# design.net
KiCad netlist of a schematic drawn in Altium Designer
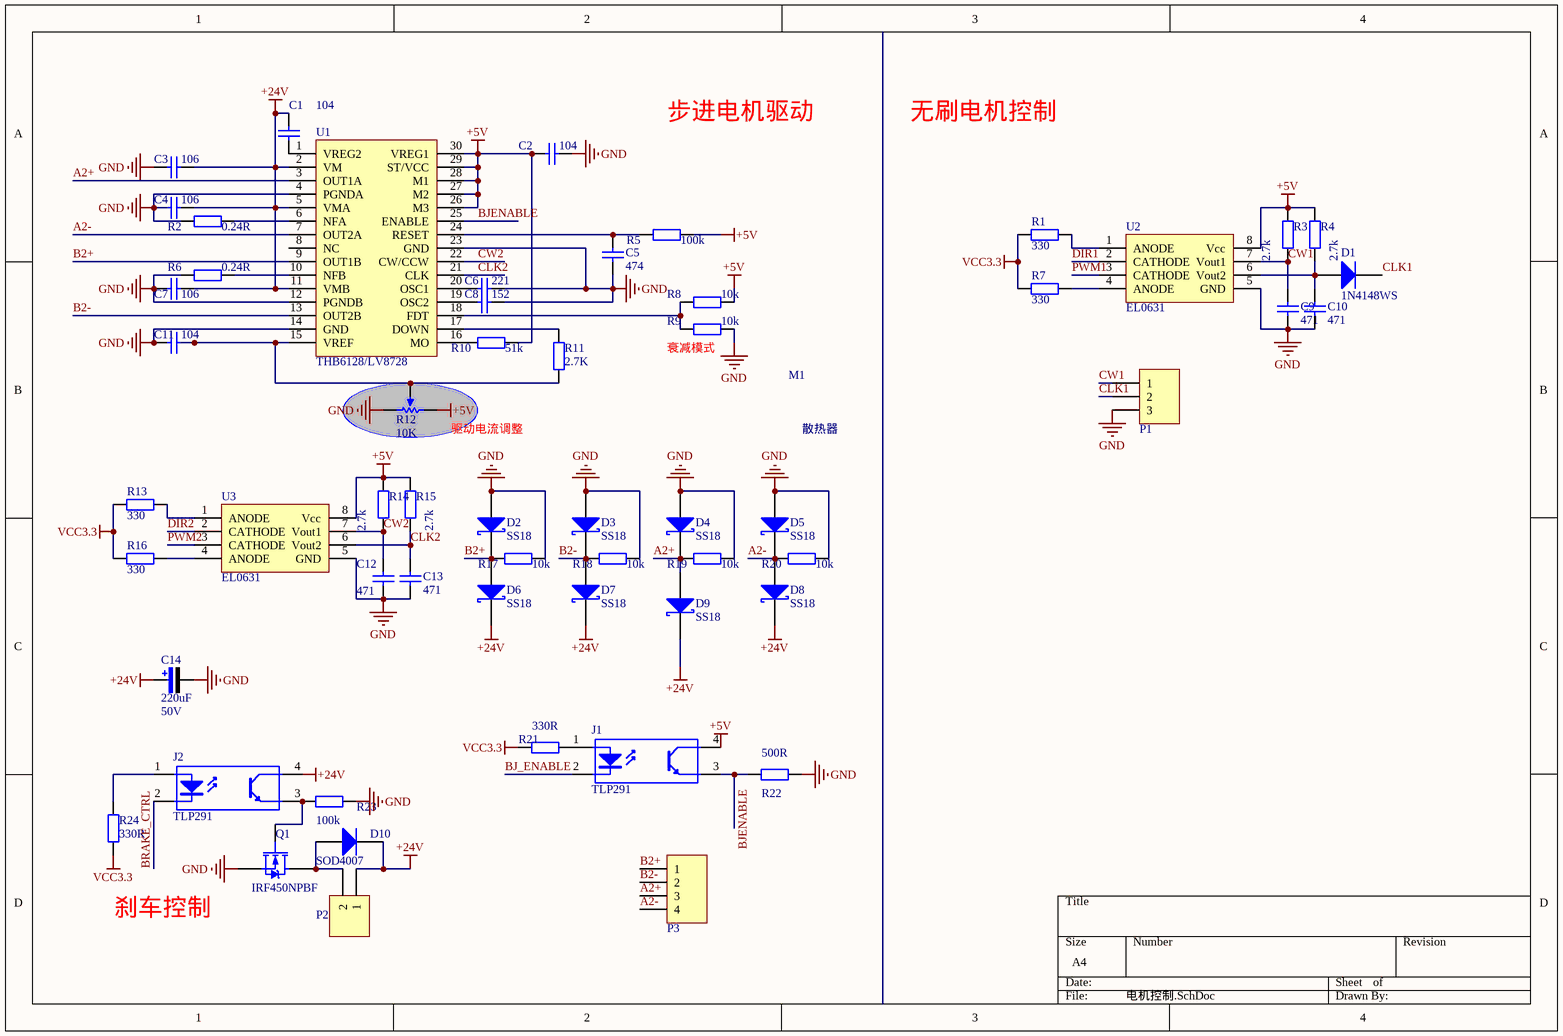
[diagram p0: 电机控制.SchDoc]

(export (version "E")
  (design (tool "Eeschema 10.0.6"))
  (components
    (comp (ref "C1")
      (value "104")
      (footprint "C-RAD-0603")
      (description "无极性电容")
      (fields (field (name "Comment") "Cap") (field (name "PUBLISHER") "Altium Limited"))
      (libsource (lib "Fszhang") (part "Cap"))
    )
    (comp (ref "C2")
      (value "104")
      (footprint "C-RAD-0603")
      (description "无极性电容")
      (fields (field (name "Comment") "Cap") (field (name "PUBLISHER") "Altium Limited"))
      (libsource (lib "Fszhang") (part "Cap"))
    )
    (comp (ref "C3")
      (value "106")
      (footprint "C-RAD-0603")
      (description "无极性电容")
      (fields (field (name "Comment") "Cap") (field (name "PUBLISHER") "Altium Limited"))
      (libsource (lib "Fszhang") (part "Cap"))
    )
    (comp (ref "C4")
      (value "106")
      (footprint "C-RAD-0603")
      (description "无极性电容")
      (fields (field (name "Comment") "Cap") (field (name "PUBLISHER") "Altium Limited"))
      (libsource (lib "Fszhang") (part "Cap"))
    )
    (comp (ref "C5")
      (value "474")
      (footprint "C-RAD-0603")
      (description "无极性电容")
      (fields (field (name "Comment") "Cap") (field (name "PUBLISHER") "Altium Limited"))
      (libsource (lib "Fszhang") (part "Cap"))
    )
    (comp (ref "C6")
      (value "221")
      (footprint "C-RAD-0603")
      (description "无极性电容")
      (fields (field (name "Comment") "Cap") (field (name "PUBLISHER") "Altium Limited"))
      (libsource (lib "Fszhang") (part "Cap"))
    )
    (comp (ref "C7")
      (value "106")
      (footprint "C-RAD-0603")
      (description "无极性电容")
      (fields (field (name "Comment") "Cap") (field (name "PUBLISHER") "Altium Limited"))
      (libsource (lib "Fszhang") (part "Cap"))
    )
    (comp (ref "C8")
      (value "152")
      (footprint "C-RAD-0603")
      (description "无极性电容")
      (fields (field (name "Comment") "Cap") (field (name "PUBLISHER") "Altium Limited"))
      (libsource (lib "Fszhang") (part "Cap"))
    )
    (comp (ref "C9")
      (value "471")
      (footprint "C-RAD-0603")
      (description "无极性电容")
      (fields (field (name "Comment") "Cap") (field (name "PUBLISHER") "Altium Limited"))
      (libsource (lib "Fszhang") (part "Cap"))
    )
    (comp (ref "C10")
      (value "471")
      (footprint "C-RAD-0603")
      (description "无极性电容")
      (fields (field (name "Comment") "Cap") (field (name "PUBLISHER") "Altium Limited"))
      (libsource (lib "Fszhang") (part "Cap"))
    )
    (comp (ref "C11")
      (value "104")
      (footprint "C-RAD-0603")
      (description "无极性电容")
      (fields (field (name "Comment") "Cap") (field (name "PUBLISHER") "Altium Limited"))
      (libsource (lib "Fszhang") (part "Cap"))
    )
    (comp (ref "C12")
      (value "471")
      (footprint "C-RAD-0603")
      (description "无极性电容")
      (fields (field (name "Comment") "Cap") (field (name "PUBLISHER") "Altium Limited"))
      (libsource (lib "Fszhang") (part "Cap"))
    )
    (comp (ref "C13")
      (value "471")
      (footprint "C-RAD-0603")
      (description "无极性电容")
      (fields (field (name "Comment") "Cap") (field (name "PUBLISHER") "Altium Limited"))
      (libsource (lib "Fszhang") (part "Cap"))
    )
    (comp (ref "C14")
      (value "220uF")
      (footprint "C-RB-S10")
      (description "极性电解电容")
      (fields
        (field (name "VOL") "50V")
        (field (name "Comment") "Cap Pol")
        (field (name "PUBLISHER") "Altium Limited")
      )
      (libsource (lib "Fszhang") (part "Cap Pol"))
    )
    (comp (ref "D1")
      (value "Diode")
      (footprint "SOD323")
      (description "二极管")
      (fields (field (name "TYPE") "1N4148WS") (field (name "PUBLISHER") "Altium Limited"))
      (libsource (lib "Fszhang") (part "Diode"))
    )
    (comp (ref "D2")
      (value "D-Schottky")
      (footprint "DIODE-SMA")
      (description "肖特基二极管")
      (fields (field (name "TYPE") "SS18") (field (name "PUBLISHER") "Altium Limited"))
      (libsource (lib "Fszhang") (part "D-Schottky"))
    )
    (comp (ref "D3")
      (value "D-Schottky")
      (footprint "DIODE-SMA")
      (description "肖特基二极管")
      (fields (field (name "TYPE") "SS18") (field (name "PUBLISHER") "Altium Limited"))
      (libsource (lib "Fszhang") (part "D-Schottky"))
    )
    (comp (ref "D4")
      (value "D-Schottky")
      (footprint "DIODE-SMA")
      (description "肖特基二极管")
      (fields (field (name "TYPE") "SS18") (field (name "PUBLISHER") "Altium Limited"))
      (libsource (lib "Fszhang") (part "D-Schottky"))
    )
    (comp (ref "D5")
      (value "D-Schottky")
      (footprint "DIODE-SMA")
      (description "肖特基二极管")
      (fields (field (name "TYPE") "SS18") (field (name "PUBLISHER") "Altium Limited"))
      (libsource (lib "Fszhang") (part "D-Schottky"))
    )
    (comp (ref "D6")
      (value "D-Schottky")
      (footprint "DIODE-SMA")
      (description "肖特基二极管")
      (fields (field (name "TYPE") "SS18") (field (name "PUBLISHER") "Altium Limited"))
      (libsource (lib "Fszhang") (part "D-Schottky"))
    )
    (comp (ref "D7")
      (value "D-Schottky")
      (footprint "DIODE-SMA")
      (description "肖特基二极管")
      (fields (field (name "TYPE") "SS18") (field (name "PUBLISHER") "Altium Limited"))
      (libsource (lib "Fszhang") (part "D-Schottky"))
    )
    (comp (ref "D8")
      (value "D-Schottky")
      (footprint "DIODE-SMA")
      (description "肖特基二极管")
      (fields (field (name "TYPE") "SS18") (field (name "PUBLISHER") "Altium Limited"))
      (libsource (lib "Fszhang") (part "D-Schottky"))
    )
    (comp (ref "D9")
      (value "D-Schottky")
      (footprint "DIODE-SMA")
      (description "肖特基二极管")
      (fields (field (name "TYPE") "SS18") (field (name "PUBLISHER") "Altium Limited"))
      (libsource (lib "Fszhang") (part "D-Schottky"))
    )
    (comp (ref "D10")
      (value "Diode")
      (footprint "SOD123")
      (description "二极管")
      (fields (field (name "TYPE") "SOD4007") (field (name "PUBLISHER") "Altium Limited"))
      (libsource (lib "Fszhang") (part "Diode"))
    )
    (comp (ref "J1")
      (value "TLP291")
      (footprint "SOP127P710X350-4N")
      (description "光耦")
      (fields (field (name "PUBLISHER") "Altium Limited"))
      (libsource (lib "Fszhang") (part "TLP281"))
    )
    (comp (ref "J2")
      (value "TLP291")
      (footprint "SOP127P710X350-4N")
      (description "光耦")
      (fields (field (name "PUBLISHER") "Altium Limited"))
      (libsource (lib "") (part "TLP281_1"))
    )
    (comp (ref "M1")
      (value "散热器")
      (footprint "26*26*10对角37.5")
      (description "26*26*10MM散热器孔距37MM")
      (libsource (lib "RADIATOR") (part "26*26*10散热器"))
    )
    (comp (ref "P1")
      (value "Header 3")
      (footprint "XH2.54*3卧贴")
      (description "接插件")
      (fields (field (name "PUBLISHER") "Altium Limited"))
      (libsource (lib "Fszhang") (part "Header 3"))
    )
    (comp (ref "P2")
      (value "Header 2")
      (footprint "XH2.54*2卧贴")
      (description "接插件")
      (fields (field (name "PUBLISHER") "Altium Limited"))
      (libsource (lib "Fszhang") (part "Header 2"))
    )
    (comp (ref "P3")
      (value "Header 4")
      (footprint "XH2.54*4卧贴")
      (description "接插件")
      (fields (field (name "PUBLISHER") "Altium Limited"))
      (libsource (lib "Fszhang") (part "Header 4"))
    )
    (comp (ref "Q1")
      (value "IRF450NPBF")
      (footprint "TO-263-2")
      (description "N-Channel MOSFET")
      (fields (field (name "PUBLISHER") "Altium Limited"))
      (libsource (lib "Fszhang") (part "MOSFET-N"))
    )
    (comp (ref "R1")
      (value "330")
      (footprint "0603-1")
      (description "贴片电阻")
      (fields (field (name "Comment") "Res1") (field (name "PUBLISHER") "Altium Limited"))
      (libsource (lib "") (part "Res1_1"))
    )
    (comp (ref "R2")
      (value "0.24R")
      (footprint "2512")
      (description "贴片电阻")
      (fields (field (name "Comment") "Res1") (field (name "PUBLISHER") "Altium Limited"))
      (libsource (lib "Fszhang") (part "Res1"))
    )
    (comp (ref "R3")
      (value "2.7k")
      (footprint "0603-1")
      (description "贴片电阻")
      (fields (field (name "Comment") "Res1") (field (name "PUBLISHER") "Altium Limited"))
      (libsource (lib "") (part "Res1_3"))
    )
    (comp (ref "R4")
      (value "2.7k")
      (footprint "0603-1")
      (description "贴片电阻")
      (fields (field (name "Comment") "Res1") (field (name "PUBLISHER") "Altium Limited"))
      (libsource (lib "") (part "Res1_3"))
    )
    (comp (ref "R5")
      (value "100k")
      (footprint "0603-1")
      (description "贴片电阻")
      (fields (field (name "Comment") "Res1") (field (name "PUBLISHER") "Altium Limited"))
      (libsource (lib "Fszhang") (part "Res1"))
    )
    (comp (ref "R6")
      (value "0.24R")
      (footprint "2512")
      (description "贴片电阻")
      (fields (field (name "Comment") "Res1") (field (name "PUBLISHER") "Altium Limited"))
      (libsource (lib "") (part "Res1_1"))
    )
    (comp (ref "R7")
      (value "330")
      (footprint "0603-1")
      (description "贴片电阻")
      (fields (field (name "Comment") "Res1") (field (name "PUBLISHER") "Altium Limited"))
      (libsource (lib "") (part "Res1_1"))
    )
    (comp (ref "R8")
      (value "10k")
      (footprint "0603-1")
      (description "贴片电阻")
      (fields (field (name "Comment") "Res1") (field (name "PUBLISHER") "Altium Limited"))
      (libsource (lib "Fszhang") (part "Res1"))
    )
    (comp (ref "R9")
      (value "10k")
      (footprint "0603-1")
      (description "贴片电阻")
      (fields (field (name "Comment") "Res1") (field (name "PUBLISHER") "Altium Limited"))
      (libsource (lib "Fszhang") (part "Res1"))
    )
    (comp (ref "R10")
      (value "51k")
      (footprint "0603-1")
      (description "贴片电阻")
      (fields (field (name "Comment") "Res1") (field (name "PUBLISHER") "Altium Limited"))
      (libsource (lib "Fszhang") (part "Res1"))
    )
    (comp (ref "R11")
      (value "2.7K")
      (footprint "0603-1")
      (description "贴片电阻")
      (fields (field (name "Comment") "Res1") (field (name "PUBLISHER") "Altium Limited"))
      (libsource (lib "") (part "Res1_2"))
    )
    (comp (ref "R12")
      (value "10K")
      (footprint "VR-3266W")
      (description "精密可调电阻")
      (fields (field (name "Comment") "RPot") (field (name "PUBLISHER") "Altium Limited"))
      (libsource (lib "Fszhang") (part "RPot"))
    )
    (comp (ref "R13")
      (value "330")
      (footprint "0603-1")
      (description "贴片电阻")
      (fields (field (name "Comment") "Res1") (field (name "PUBLISHER") "Altium Limited"))
      (libsource (lib "") (part "Res1_1"))
    )
    (comp (ref "R14")
      (value "2.7k")
      (footprint "0603-1")
      (description "贴片电阻")
      (fields (field (name "Comment") "Res1") (field (name "PUBLISHER") "Altium Limited"))
      (libsource (lib "") (part "Res1_3"))
    )
    (comp (ref "R15")
      (value "2.7k")
      (footprint "0603-1")
      (description "贴片电阻")
      (fields (field (name "Comment") "Res1") (field (name "PUBLISHER") "Altium Limited"))
      (libsource (lib "") (part "Res1_3"))
    )
    (comp (ref "R16")
      (value "330")
      (footprint "0603-1")
      (description "贴片电阻")
      (fields (field (name "Comment") "Res1") (field (name "PUBLISHER") "Altium Limited"))
      (libsource (lib "") (part "Res1_1"))
    )
    (comp (ref "R17")
      (value "10k")
      (footprint "0603-1")
      (description "贴片电阻")
      (fields (field (name "Comment") "Res1") (field (name "PUBLISHER") "Altium Limited"))
      (libsource (lib "Fszhang") (part "Res1"))
    )
    (comp (ref "R18")
      (value "10k")
      (footprint "0603-1")
      (description "贴片电阻")
      (fields (field (name "Comment") "Res1") (field (name "PUBLISHER") "Altium Limited"))
      (libsource (lib "Fszhang") (part "Res1"))
    )
    (comp (ref "R19")
      (value "10k")
      (footprint "0603-1")
      (description "贴片电阻")
      (fields (field (name "Comment") "Res1") (field (name "PUBLISHER") "Altium Limited"))
      (libsource (lib "Fszhang") (part "Res1"))
    )
    (comp (ref "R20")
      (value "10k")
      (footprint "0603-1")
      (description "贴片电阻")
      (fields (field (name "Comment") "Res1") (field (name "PUBLISHER") "Altium Limited"))
      (libsource (lib "Fszhang") (part "Res1"))
    )
    (comp (ref "R21")
      (value "330R")
      (footprint "0603-1")
      (description "贴片电阻")
      (fields (field (name "Comment") "Res1") (field (name "PUBLISHER") "Altium Limited"))
      (libsource (lib "") (part "Res1_1"))
    )
    (comp (ref "R22")
      (value "500R")
      (footprint "0603-1")
      (description "贴片电阻")
      (fields (field (name "Comment") "Res1") (field (name "PUBLISHER") "Altium Limited"))
      (libsource (lib "") (part "Res1_1"))
    )
    (comp (ref "R23")
      (value "100k")
      (footprint "0603-1")
      (description "贴片电阻")
      (fields (field (name "Comment") "Res1") (field (name "PUBLISHER") "Altium Limited"))
      (libsource (lib "") (part "Res1_1"))
    )
    (comp (ref "R24")
      (value "330R")
      (footprint "0603-1")
      (description "贴片电阻")
      (fields (field (name "Comment") "Res1") (field (name "PUBLISHER") "Altium Limited"))
      (libsource (lib "") (part "Res1_2"))
    )
    (comp (ref "U1")
      (value "THB6128/LV8728")
      (footprint "SIOC-30-W")
      (description "步进电机驱动")
      (libsource (lib "Fszhang") (part "THB6128"))
    )
    (comp (ref "U2")
      (value "EL0631")
      (footprint "EL0631")
      (description "双路隔离光耦")
      (libsource (lib "Fszhang") (part "EL0631"))
    )
    (comp (ref "U3")
      (value "EL0631")
      (footprint "EL0631")
      (description "双路隔离光耦")
      (libsource (lib "Fszhang") (part "EL0631"))
    )
  )
  (nets
    (net (code "1") (name "+5V") (class "Default")
      (node (ref "C2") (pin "1") (pinfunction "1_1") (pintype "passive"))
      (node (ref "J1") (pin "4") (pinfunction "C_4") (pintype "passive"))
      (node (ref "R10") (pin "2") (pinfunction "2_2") (pintype "passive"))
      (node (ref "R12") (pin "1") (pinfunction "TOP_1") (pintype "passive"))
      (node (ref "R14") (pin "2") (pinfunction "2_2") (pintype "passive"))
      (node (ref "R15") (pin "2") (pinfunction "2_2") (pintype "passive"))
      (node (ref "R3") (pin "2") (pinfunction "2_2") (pintype "passive"))
      (node (ref "R4") (pin "2") (pinfunction "2_2") (pintype "passive"))
      (node (ref "R5") (pin "2") (pinfunction "2_2") (pintype "passive"))
      (node (ref "R8") (pin "2") (pinfunction "2_2") (pintype "passive"))
      (node (ref "U1") (pin "26") (pinfunction "M3_26") (pintype "passive"))
      (node (ref "U1") (pin "27") (pinfunction "M2_27") (pintype "passive"))
      (node (ref "U1") (pin "28") (pinfunction "M1_28") (pintype "passive"))
      (node (ref "U1") (pin "29") (pinfunction "ST/VCC_29") (pintype "passive"))
      (node (ref "U1") (pin "30") (pinfunction "VREG1_30") (pintype "passive"))
      (node (ref "U2") (pin "8") (pinfunction "Vcc_8") (pintype "passive"))
      (node (ref "U3") (pin "8") (pinfunction "Vcc_8") (pintype "passive"))
    )
    (net (code "2") (name "+24V") (class "Default")
      (node (ref "C1") (pin "1") (pinfunction "1_1") (pintype "passive"))
      (node (ref "C14") (pin "1") (pinfunction "1_1") (pintype "passive"))
      (node (ref "C3") (pin "2") (pinfunction "2_2") (pintype "passive"))
      (node (ref "C4") (pin "2") (pinfunction "2_2") (pintype "passive"))
      (node (ref "C7") (pin "2") (pinfunction "2_2") (pintype "passive"))
      (node (ref "D10") (pin "2") (pinfunction "K_2") (pintype "passive"))
      (node (ref "D6") (pin "2") (pinfunction "K_2") (pintype "passive"))
      (node (ref "D7") (pin "2") (pinfunction "K_2") (pintype "passive"))
      (node (ref "D8") (pin "2") (pinfunction "K_2") (pintype "passive"))
      (node (ref "D9") (pin "2") (pinfunction "K_2") (pintype "passive"))
      (node (ref "J2") (pin "4") (pinfunction "C_4") (pintype "passive"))
      (node (ref "P2") (pin "1") (pinfunction "1_1") (pintype "passive"))
      (node (ref "U1") (pin "11") (pinfunction "VMB_11") (pintype "passive"))
      (node (ref "U1") (pin "2") (pinfunction "VM_2") (pintype "passive"))
      (node (ref "U1") (pin "5") (pinfunction "VMA_5") (pintype "passive"))
    )
    (net (code "3") (name "/A2+") (class "Default")
      (node (ref "D4") (pin "2") (pinfunction "K_2") (pintype "passive"))
      (node (ref "D9") (pin "1") (pinfunction "A_1") (pintype "passive"))
      (node (ref "P3") (pin "3") (pinfunction "3_3") (pintype "passive"))
      (node (ref "R19") (pin "1") (pinfunction "1_1") (pintype "passive"))
      (node (ref "U1") (pin "3") (pinfunction "OUT1A_3") (pintype "passive"))
    )
    (net (code "4") (name "/A2-") (class "Default")
      (node (ref "D5") (pin "2") (pinfunction "K_2") (pintype "passive"))
      (node (ref "D8") (pin "1") (pinfunction "A_1") (pintype "passive"))
      (node (ref "P3") (pin "4") (pinfunction "4_4") (pintype "passive"))
      (node (ref "R20") (pin "1") (pinfunction "1_1") (pintype "passive"))
      (node (ref "U1") (pin "7") (pinfunction "OUT2A_7") (pintype "passive"))
    )
    (net (code "5") (name "/B2+") (class "Default")
      (node (ref "D2") (pin "2") (pinfunction "K_2") (pintype "passive"))
      (node (ref "D6") (pin "1") (pinfunction "A_1") (pintype "passive"))
      (node (ref "P3") (pin "1") (pinfunction "1_1") (pintype "passive"))
      (node (ref "R17") (pin "1") (pinfunction "1_1") (pintype "passive"))
      (node (ref "U1") (pin "9") (pinfunction "OUT1B_9") (pintype "passive"))
    )
    (net (code "6") (name "/B2-") (class "Default")
      (node (ref "D3") (pin "2") (pinfunction "K_2") (pintype "passive"))
      (node (ref "D7") (pin "1") (pinfunction "A_1") (pintype "passive"))
      (node (ref "P3") (pin "2") (pinfunction "2_2") (pintype "passive"))
      (node (ref "R18") (pin "1") (pinfunction "1_1") (pintype "passive"))
      (node (ref "U1") (pin "13") (pinfunction "OUT2B_13") (pintype "passive"))
    )
    (net (code "7") (name "/BJENABLE") (class "Default")
      (node (ref "J1") (pin "3") (pinfunction "E_3") (pintype "passive"))
      (node (ref "R22") (pin "2") (pinfunction "2_2") (pintype "passive"))
      (node (ref "U1") (pin "25") (pinfunction "ENABLE_25") (pintype "passive"))
    )
    (net (code "8") (name "/BJ_ENABLE") (class "Default")
      (node (ref "J1") (pin "2") (pinfunction "K_2") (pintype "passive"))
    )
    (net (code "9") (name "/BRAKE_CTRL") (class "Default")
      (node (ref "J2") (pin "2") (pinfunction "K_2") (pintype "passive"))
    )
    (net (code "10") (name "/CLK1") (class "Default")
      (node (ref "D1") (pin "2") (pinfunction "K_2") (pintype "passive"))
      (node (ref "P1") (pin "2") (pinfunction "2_2") (pintype "passive"))
    )
    (net (code "11") (name "/CLK2") (class "Default")
      (node (ref "C13") (pin "2") (pinfunction "2_2") (pintype "passive"))
      (node (ref "R15") (pin "1") (pinfunction "1_1") (pintype "passive"))
      (node (ref "U1") (pin "21") (pinfunction "CLK_21") (pintype "passive"))
      (node (ref "U3") (pin "6") (pinfunction "Vout2_6") (pintype "passive"))
    )
    (net (code "12") (name "/CW1") (class "Default")
      (node (ref "C9") (pin "2") (pinfunction "2_2") (pintype "passive"))
      (node (ref "P1") (pin "1") (pinfunction "1_1") (pintype "passive"))
      (node (ref "R3") (pin "1") (pinfunction "1_1") (pintype "passive"))
      (node (ref "U2") (pin "7") (pinfunction "Vout1_7") (pintype "passive"))
    )
    (net (code "13") (name "/CW2") (class "Default")
      (node (ref "C12") (pin "2") (pinfunction "2_2") (pintype "passive"))
      (node (ref "R14") (pin "1") (pinfunction "1_1") (pintype "passive"))
      (node (ref "U1") (pin "22") (pinfunction "CW/CCW_22") (pintype "passive"))
      (node (ref "U3") (pin "7") (pinfunction "Vout1_7") (pintype "passive"))
    )
    (net (code "14") (name "/DIR1") (class "Default")
      (node (ref "U2") (pin "2") (pinfunction "CATHODE_2") (pintype "passive"))
    )
    (net (code "15") (name "/DIR2") (class "Default")
      (node (ref "U3") (pin "2") (pinfunction "CATHODE_2") (pintype "passive"))
    )
    (net (code "16") (name "/PWM1") (class "Default")
      (node (ref "U2") (pin "3") (pinfunction "CATHODE_3") (pintype "passive"))
    )
    (net (code "17") (name "/PWM2") (class "Default")
      (node (ref "U3") (pin "3") (pinfunction "CATHODE_3") (pintype "passive"))
    )
    (net (code "18") (name "GND") (class "Default")
      (node (ref "C10") (pin "1") (pinfunction "1_1") (pintype "passive"))
      (node (ref "C11") (pin "1") (pinfunction "1_1") (pintype "passive"))
      (node (ref "C12") (pin "1") (pinfunction "1_1") (pintype "passive"))
      (node (ref "C13") (pin "1") (pinfunction "1_1") (pintype "passive"))
      (node (ref "C14") (pin "2") (pinfunction "2_2") (pintype "passive"))
      (node (ref "C2") (pin "2") (pinfunction "2_2") (pintype "passive"))
      (node (ref "C3") (pin "1") (pinfunction "1_1") (pintype "passive"))
      (node (ref "C4") (pin "1") (pinfunction "1_1") (pintype "passive"))
      (node (ref "C5") (pin "1") (pinfunction "1_1") (pintype "passive"))
      (node (ref "C6") (pin "2") (pinfunction "2_2") (pintype "passive"))
      (node (ref "C7") (pin "1") (pinfunction "1_1") (pintype "passive"))
      (node (ref "C8") (pin "2") (pinfunction "2_2") (pintype "passive"))
      (node (ref "C9") (pin "1") (pinfunction "1_1") (pintype "passive"))
      (node (ref "D2") (pin "1") (pinfunction "A_1") (pintype "passive"))
      (node (ref "D3") (pin "1") (pinfunction "A_1") (pintype "passive"))
      (node (ref "D4") (pin "1") (pinfunction "A_1") (pintype "passive"))
      (node (ref "D5") (pin "1") (pinfunction "A_1") (pintype "passive"))
      (node (ref "P1") (pin "3") (pinfunction "3_3") (pintype "passive"))
      (node (ref "Q1") (pin "2") (pinfunction "S_2") (pintype "passive"))
      (node (ref "R12") (pin "3") (pinfunction "BOT_3") (pintype "passive"))
      (node (ref "R17") (pin "2") (pinfunction "2_2") (pintype "passive"))
      (node (ref "R18") (pin "2") (pinfunction "2_2") (pintype "passive"))
      (node (ref "R19") (pin "2") (pinfunction "2_2") (pintype "passive"))
      (node (ref "R2") (pin "1") (pinfunction "1_1") (pintype "passive"))
      (node (ref "R20") (pin "2") (pinfunction "2_2") (pintype "passive"))
      (node (ref "R22") (pin "1") (pinfunction "1_1") (pintype "passive"))
      (node (ref "R23") (pin "1") (pinfunction "1_1") (pintype "passive"))
      (node (ref "R6") (pin "2") (pinfunction "2_2") (pintype "passive"))
      (node (ref "R9") (pin "2") (pinfunction "2_2") (pintype "passive"))
      (node (ref "U1") (pin "12") (pinfunction "PGNDB_12") (pintype "passive"))
      (node (ref "U1") (pin "14") (pinfunction "GND_14") (pintype "passive"))
      (node (ref "U1") (pin "23") (pinfunction "GND_23") (pintype "passive"))
      (node (ref "U1") (pin "4") (pinfunction "PGNDA_4") (pintype "passive"))
      (node (ref "U2") (pin "5") (pinfunction "GND_5") (pintype "passive"))
      (node (ref "U3") (pin "5") (pinfunction "GND_5") (pintype "passive"))
    )
    (net (code "19") (name "Net-(D1-A)") (class "Default")
      (node (ref "C10") (pin "2") (pinfunction "2_2") (pintype "passive"))
      (node (ref "D1") (pin "1") (pinfunction "A_1") (pintype "passive"))
      (node (ref "R4") (pin "1") (pinfunction "1_1") (pintype "passive"))
      (node (ref "U2") (pin "6") (pinfunction "Vout2_6") (pintype "passive"))
    )
    (net (code "20") (name "Net-(D10-A)") (class "Default")
      (node (ref "D10") (pin "1") (pinfunction "A_1") (pintype "passive"))
      (node (ref "P2") (pin "2") (pinfunction "2_2") (pintype "passive"))
      (node (ref "Q1") (pin "3") (pinfunction "D_3") (pintype "passive"))
    )
    (net (code "21") (name "Net-(J1-A)") (class "Default")
      (node (ref "J1") (pin "1") (pinfunction "A_1") (pintype "passive"))
      (node (ref "R21") (pin "1") (pinfunction "1_1") (pintype "passive"))
    )
    (net (code "22") (name "Net-(J2-A)") (class "Default")
      (node (ref "J2") (pin "1") (pinfunction "A_1") (pintype "passive"))
      (node (ref "R24") (pin "1") (pinfunction "1_1") (pintype "passive"))
    )
    (net (code "23") (name "Net-(J2-E)") (class "Default")
      (node (ref "J2") (pin "3") (pinfunction "E_3") (pintype "passive"))
      (node (ref "Q1") (pin "1") (pinfunction "G_1") (pintype "passive"))
      (node (ref "R23") (pin "2") (pinfunction "2_2") (pintype "passive"))
    )
    (net (code "24") (name "Net-(R1-Pad1)") (class "Default")
      (node (ref "R1") (pin "1") (pinfunction "1_1") (pintype "passive"))
      (node (ref "U2") (pin "1") (pinfunction "ANODE_1") (pintype "passive"))
    )
    (net (code "25") (name "Net-(R7-Pad1)") (class "Default")
      (node (ref "R7") (pin "1") (pinfunction "1_1") (pintype "passive"))
      (node (ref "U2") (pin "4") (pinfunction "ANODE_4") (pintype "passive"))
    )
    (net (code "26") (name "Net-(R12-TAP)") (class "Default")
      (node (ref "C11") (pin "2") (pinfunction "2_2") (pintype "passive"))
      (node (ref "R11") (pin "2") (pinfunction "2_2") (pintype "passive"))
      (node (ref "R12") (pin "2") (pinfunction "TAP_2") (pintype "passive"))
      (node (ref "U1") (pin "15") (pinfunction "VREF_15") (pintype "passive"))
    )
    (net (code "27") (name "Net-(R13-Pad1)") (class "Default")
      (node (ref "R13") (pin "1") (pinfunction "1_1") (pintype "passive"))
      (node (ref "U3") (pin "1") (pinfunction "ANODE_1") (pintype "passive"))
    )
    (net (code "28") (name "Net-(R16-Pad1)") (class "Default")
      (node (ref "R16") (pin "1") (pinfunction "1_1") (pintype "passive"))
      (node (ref "U3") (pin "4") (pinfunction "ANODE_4") (pintype "passive"))
    )
    (net (code "29") (name "Net-(U1-DOWN)") (class "Default")
      (node (ref "R11") (pin "1") (pinfunction "1_1") (pintype "passive"))
      (node (ref "U1") (pin "17") (pinfunction "DOWN_17") (pintype "passive"))
    )
    (net (code "30") (name "Net-(U1-FDT)") (class "Default")
      (node (ref "R8") (pin "1") (pinfunction "1_1") (pintype "passive"))
      (node (ref "R9") (pin "1") (pinfunction "1_1") (pintype "passive"))
      (node (ref "U1") (pin "18") (pinfunction "FDT_18") (pintype "passive"))
    )
    (net (code "31") (name "Net-(U1-MO)") (class "Default")
      (node (ref "R10") (pin "1") (pinfunction "1_1") (pintype "passive"))
      (node (ref "U1") (pin "16") (pinfunction "MO_16") (pintype "passive"))
    )
    (net (code "32") (name "Net-(U1-NFA)") (class "Default")
      (node (ref "R2") (pin "2") (pinfunction "2_2") (pintype "passive"))
      (node (ref "U1") (pin "6") (pinfunction "NFA_6") (pintype "passive"))
    )
    (net (code "33") (name "Net-(U1-NFB)") (class "Default")
      (node (ref "R6") (pin "1") (pinfunction "1_1") (pintype "passive"))
      (node (ref "U1") (pin "10") (pinfunction "NFB_10") (pintype "passive"))
    )
    (net (code "34") (name "Net-(U1-OSC1)") (class "Default")
      (node (ref "C6") (pin "1") (pinfunction "1_1") (pintype "passive"))
      (node (ref "U1") (pin "20") (pinfunction "OSC1_20") (pintype "passive"))
    )
    (net (code "35") (name "Net-(U1-OSC2)") (class "Default")
      (node (ref "C8") (pin "1") (pinfunction "1_1") (pintype "passive"))
      (node (ref "U1") (pin "19") (pinfunction "OSC2_19") (pintype "passive"))
    )
    (net (code "36") (name "Net-(U1-RESET)") (class "Default")
      (node (ref "C5") (pin "2") (pinfunction "2_2") (pintype "passive"))
      (node (ref "R5") (pin "1") (pinfunction "1_1") (pintype "passive"))
      (node (ref "U1") (pin "24") (pinfunction "RESET_24") (pintype "passive"))
    )
    (net (code "37") (name "Net-(U1-VREG2)") (class "Default")
      (node (ref "C1") (pin "2") (pinfunction "2_2") (pintype "passive"))
      (node (ref "U1") (pin "1") (pinfunction "VREG2_1") (pintype "passive"))
    )
    (net (code "38") (name "VCC3.3") (class "Default")
      (node (ref "R1") (pin "2") (pinfunction "2_2") (pintype "passive"))
      (node (ref "R13") (pin "2") (pinfunction "2_2") (pintype "passive"))
      (node (ref "R16") (pin "2") (pinfunction "2_2") (pintype "passive"))
      (node (ref "R21") (pin "2") (pinfunction "2_2") (pintype "passive"))
      (node (ref "R24") (pin "2") (pinfunction "2_2") (pintype "passive"))
      (node (ref "R7") (pin "2") (pinfunction "2_2") (pintype "passive"))
    )
    (net (code "39") (name "unconnected-(U1-NC-Pad8)") (class "Default")
      (node (ref "U1") (pin "8") (pinfunction "NC_8") (pintype "passive"))
    )
  )
)
